# 3StepV1.net
KiCad netlist of a schematic drawn in EAGLE
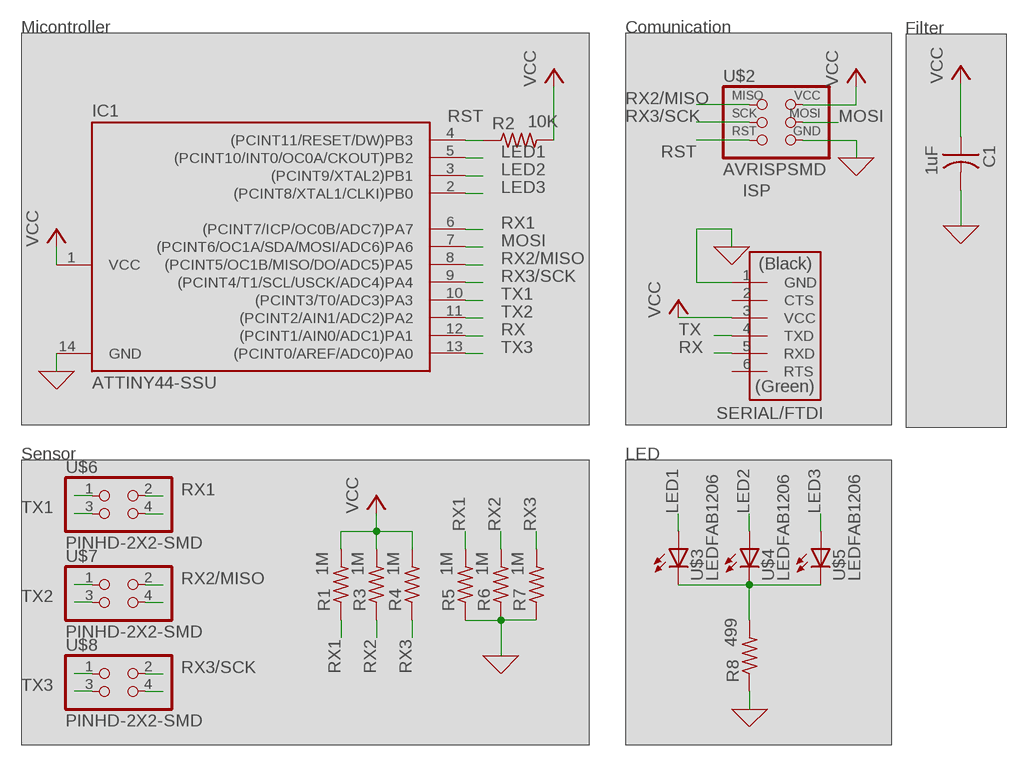
[diagram p0: schematic, sheet 1]

(export (version "E")
  (design (tool "Eeschema 10.0.6"))
  (components
    (comp (ref "C1")
      (value "1uF")
      (footprint "eagle-import:C1206FAB")
      (libsource (lib "eagle-import") (part "CAP-US1206FAB"))
    )
    (comp (ref "IC1")
      (value "ATTINY44-SSU")
      (footprint "eagle-import:SOIC14")
      (libsource (lib "eagle-import") (part "ATTINY44-SSU"))
    )
    (comp (ref "R1")
      (value "1M")
      (footprint "eagle-import:R1206FAB")
      (libsource (lib "eagle-import") (part "RES-US1206FAB"))
    )
    (comp (ref "R2")
      (value "10K")
      (footprint "eagle-import:R1206FAB")
      (libsource (lib "eagle-import") (part "RES-US1206FAB"))
    )
    (comp (ref "R3")
      (value "1M")
      (footprint "eagle-import:R1206FAB")
      (libsource (lib "eagle-import") (part "RES-US1206FAB"))
    )
    (comp (ref "R4")
      (value "1M")
      (footprint "eagle-import:R1206FAB")
      (libsource (lib "eagle-import") (part "RES-US1206FAB"))
    )
    (comp (ref "R5")
      (value "1M")
      (footprint "eagle-import:R1206FAB")
      (libsource (lib "eagle-import") (part "RES-US1206FAB"))
    )
    (comp (ref "R6")
      (value "1M")
      (footprint "eagle-import:R1206FAB")
      (libsource (lib "eagle-import") (part "RES-US1206FAB"))
    )
    (comp (ref "R7")
      (value "1M")
      (footprint "eagle-import:R1206FAB")
      (libsource (lib "eagle-import") (part "RES-US1206FAB"))
    )
    (comp (ref "R8")
      (value "499")
      (footprint "eagle-import:R1206FAB")
      (libsource (lib "eagle-import") (part "RES-US1206FAB"))
    )
    (comp (ref "U$1")
      (value "FTDI-SMD-HEADER")
      (footprint "eagle-import:1X06SMD")
      (libsource (lib "eagle-import") (part "FTDI-SMD-HEADER"))
    )
    (comp (ref "U$2")
      (value "AVRISPSMD")
      (footprint "eagle-import:2X03SMD")
      (libsource (lib "eagle-import") (part "AVRISPSMD"))
    )
    (comp (ref "U$3")
      (value "LEDFAB1206")
      (footprint "eagle-import:LED1206FAB")
      (libsource (lib "eagle-import") (part "LEDFAB1206"))
    )
    (comp (ref "U$4")
      (value "LEDFAB1206")
      (footprint "eagle-import:LED1206FAB")
      (libsource (lib "eagle-import") (part "LEDFAB1206"))
    )
    (comp (ref "U$5")
      (value "LEDFAB1206")
      (footprint "eagle-import:LED1206FAB")
      (libsource (lib "eagle-import") (part "LEDFAB1206"))
    )
    (comp (ref "U$6")
      (value "PINHD-2X2-SMD")
      (footprint "eagle-import:2X02SMD")
      (libsource (lib "eagle-import") (part "PINHD-2X2-SMD"))
    )
    (comp (ref "U$7")
      (value "PINHD-2X2-SMD")
      (footprint "eagle-import:2X02SMD")
      (libsource (lib "eagle-import") (part "PINHD-2X2-SMD"))
    )
    (comp (ref "U$8")
      (value "PINHD-2X2-SMD")
      (footprint "eagle-import:2X02SMD")
      (libsource (lib "eagle-import") (part "PINHD-2X2-SMD"))
    )
  )
  (nets
    (net (code "1") (name "/LED1") (class "Default")
      (node (ref "IC1") (pin "5") (pinfunction "(PCINT10/INT0/OC0A/CKOUT)PB2_5") (pintype "bidirectional"))
      (node (ref "U$3") (pin "1") (pinfunction "A_1") (pintype "passive"))
    )
    (net (code "2") (name "/LED2") (class "Default")
      (node (ref "IC1") (pin "3") (pinfunction "(PCINT9/XTAL2)PB1_3") (pintype "bidirectional"))
      (node (ref "U$4") (pin "1") (pinfunction "A_1") (pintype "passive"))
    )
    (net (code "3") (name "/LED3") (class "Default")
      (node (ref "IC1") (pin "2") (pinfunction "(PCINT8/XTAL1/CLKI)PB0_2") (pintype "bidirectional"))
      (node (ref "U$5") (pin "1") (pinfunction "A_1") (pintype "passive"))
    )
    (net (code "4") (name "/MOSI") (class "Default")
      (node (ref "IC1") (pin "7") (pinfunction "(PCINT6/OC1A/SDA/MOSI/ADC6)PA6_7") (pintype "bidirectional"))
      (node (ref "U$2") (pin "4") (pinfunction "MOSI_4") (pintype "passive"))
    )
    (net (code "5") (name "/RST") (class "Default")
      (node (ref "IC1") (pin "4") (pinfunction "(PCINT11/RESET/DW)PB3_4") (pintype "bidirectional"))
      (node (ref "R2") (pin "1") (pinfunction "1_1") (pintype "passive"))
      (node (ref "U$2") (pin "5") (pinfunction "RST_5") (pintype "passive"))
    )
    (net (code "6") (name "/RX") (class "Default")
      (node (ref "IC1") (pin "12") (pinfunction "(PCINT1/AIN0/ADC1)PA1_12") (pintype "bidirectional"))
      (node (ref "U$1") (pin "5") (pinfunction "RXD_5") (pintype "bidirectional"))
    )
    (net (code "7") (name "/RX1") (class "Default")
      (node (ref "IC1") (pin "6") (pinfunction "(PCINT7/ICP/OC0B/ADC7)PA7_6") (pintype "bidirectional"))
      (node (ref "R1") (pin "1") (pinfunction "1_1") (pintype "passive"))
      (node (ref "R5") (pin "2") (pinfunction "2_2") (pintype "passive"))
      (node (ref "U$6") (pin "2") (pinfunction "2_2") (pintype "passive"))
    )
    (net (code "8") (name "/RX2") (class "Default")
      (node (ref "R3") (pin "1") (pinfunction "1_1") (pintype "passive"))
      (node (ref "R6") (pin "2") (pinfunction "2_2") (pintype "passive"))
    )
    (net (code "9") (name "/RX2{slash}MISO") (class "Default")
      (node (ref "IC1") (pin "8") (pinfunction "(PCINT5/OC1B/MISO/DO/ADC5)PA5_8") (pintype "bidirectional"))
      (node (ref "U$2") (pin "1") (pinfunction "MISO_1") (pintype "passive"))
      (node (ref "U$7") (pin "2") (pinfunction "2_2") (pintype "passive"))
    )
    (net (code "10") (name "/RX3") (class "Default")
      (node (ref "R4") (pin "1") (pinfunction "1_1") (pintype "passive"))
      (node (ref "R7") (pin "2") (pinfunction "2_2") (pintype "passive"))
    )
    (net (code "11") (name "/RX3{slash}SCK") (class "Default")
      (node (ref "IC1") (pin "9") (pinfunction "(PCINT4/T1/SCL/USCK/ADC4)PA4_9") (pintype "bidirectional"))
      (node (ref "U$2") (pin "3") (pinfunction "SCK_3") (pintype "passive"))
      (node (ref "U$8") (pin "2") (pinfunction "2_2") (pintype "passive"))
    )
    (net (code "12") (name "/TX") (class "Default")
      (node (ref "U$1") (pin "4") (pinfunction "TXD_4") (pintype "bidirectional"))
    )
    (net (code "13") (name "/TX1") (class "Default")
      (node (ref "IC1") (pin "10") (pinfunction "(PCINT3/T0/ADC3)PA3_10") (pintype "bidirectional"))
      (node (ref "U$6") (pin "3") (pinfunction "3_3") (pintype "passive"))
    )
    (net (code "14") (name "/TX2") (class "Default")
      (node (ref "IC1") (pin "11") (pinfunction "(PCINT2/AIN1/ADC2)PA2_11") (pintype "bidirectional"))
      (node (ref "U$7") (pin "3") (pinfunction "3_3") (pintype "passive"))
    )
    (net (code "15") (name "/TX3") (class "Default")
      (node (ref "IC1") (pin "13") (pinfunction "(PCINT0/AREF/ADC0)PA0_13") (pintype "bidirectional"))
      (node (ref "U$8") (pin "3") (pinfunction "3_3") (pintype "passive"))
    )
    (net (code "16") (name "GND") (class "Default")
      (node (ref "C1") (pin "2") (pinfunction "2_2") (pintype "passive"))
      (node (ref "IC1") (pin "14") (pinfunction "GND_14") (pintype "power_in"))
      (node (ref "R5") (pin "1") (pinfunction "1_1") (pintype "passive"))
      (node (ref "R6") (pin "1") (pinfunction "1_1") (pintype "passive"))
      (node (ref "R7") (pin "1") (pinfunction "1_1") (pintype "passive"))
      (node (ref "R8") (pin "1") (pinfunction "1_1") (pintype "passive"))
      (node (ref "U$1") (pin "1") (pinfunction "GND_1") (pintype "bidirectional"))
      (node (ref "U$2") (pin "6") (pinfunction "GND_6") (pintype "passive"))
    )
    (net (code "17") (name "Net-(U$3-C)") (class "Default")
      (node (ref "R8") (pin "2") (pinfunction "2_2") (pintype "passive"))
      (node (ref "U$3") (pin "2") (pinfunction "C_2") (pintype "passive"))
      (node (ref "U$4") (pin "2") (pinfunction "C_2") (pintype "passive"))
      (node (ref "U$5") (pin "2") (pinfunction "C_2") (pintype "passive"))
    )
    (net (code "18") (name "VCC") (class "Default")
      (node (ref "C1") (pin "1") (pinfunction "1_1") (pintype "passive"))
      (node (ref "IC1") (pin "1") (pinfunction "VCC_1") (pintype "power_in"))
      (node (ref "R1") (pin "2") (pinfunction "2_2") (pintype "passive"))
      (node (ref "R2") (pin "2") (pinfunction "2_2") (pintype "passive"))
      (node (ref "R3") (pin "2") (pinfunction "2_2") (pintype "passive"))
      (node (ref "R4") (pin "2") (pinfunction "2_2") (pintype "passive"))
      (node (ref "U$1") (pin "3") (pinfunction "VCC_3") (pintype "bidirectional"))
      (node (ref "U$2") (pin "2") (pinfunction "VCC_2") (pintype "passive"))
    )
    (net (code "19") (name "unconnected-(U$1-CTS-Pad2)") (class "Default")
      (node (ref "U$1") (pin "2") (pinfunction "CTS_2") (pintype "bidirectional"))
    )
    (net (code "20") (name "unconnected-(U$1-RTS-Pad6)") (class "Default")
      (node (ref "U$1") (pin "6") (pinfunction "RTS_6") (pintype "bidirectional"))
    )
    (net (code "21") (name "unconnected-(U$6-Pad1)") (class "Default")
      (node (ref "U$6") (pin "1") (pinfunction "1_1") (pintype "passive"))
    )
    (net (code "22") (name "unconnected-(U$6-Pad4)") (class "Default")
      (node (ref "U$6") (pin "4") (pinfunction "4_4") (pintype "passive"))
    )
    (net (code "23") (name "unconnected-(U$7-Pad1)") (class "Default")
      (node (ref "U$7") (pin "1") (pinfunction "1_1") (pintype "passive"))
    )
    (net (code "24") (name "unconnected-(U$7-Pad4)") (class "Default")
      (node (ref "U$7") (pin "4") (pinfunction "4_4") (pintype "passive"))
    )
    (net (code "25") (name "unconnected-(U$8-Pad1)") (class "Default")
      (node (ref "U$8") (pin "1") (pinfunction "1_1") (pintype "passive"))
    )
    (net (code "26") (name "unconnected-(U$8-Pad4)") (class "Default")
      (node (ref "U$8") (pin "4") (pinfunction "4_4") (pintype "passive"))
    )
  )
)
